# pcb5.net
KiCad netlist of a schematic drawn in EAGLE
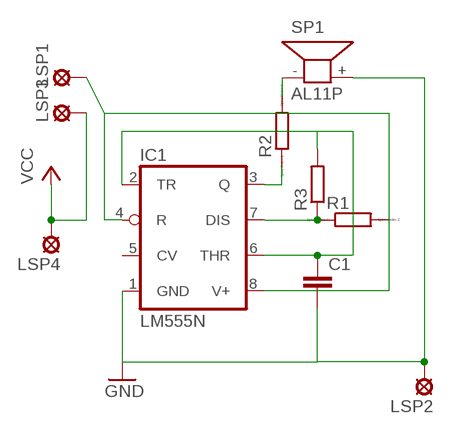
[diagram p0: schematic, sheet 1]

(export (version "E")
  (design (tool "Eeschema 10.0.6"))
  (components
    (comp (ref "C1")
      (value "C-EU025-024X044")
      (footprint "eagle-import:C025-024X044")
      (libsource (lib "eagle-import") (part "C-EU025-024X044"))
    )
    (comp (ref "IC1")
      (value "LM555N")
      (footprint "eagle-import:DIL08")
      (libsource (lib "eagle-import") (part "555NLM"))
    )
    (comp (ref "LSP1")
      (value "MCS08")
      (footprint "eagle-import:MCS08")
      (libsource (lib "eagle-import") (part "MCS08"))
    )
    (comp (ref "LSP2")
      (value "MCS08")
      (footprint "eagle-import:MCS08")
      (libsource (lib "eagle-import") (part "MCS08"))
    )
    (comp (ref "LSP3")
      (value "MCS08")
      (footprint "eagle-import:MCS08")
      (libsource (lib "eagle-import") (part "MCS08"))
    )
    (comp (ref "LSP4")
      (value "MCS08")
      (footprint "eagle-import:MCS08")
      (libsource (lib "eagle-import") (part "MCS08"))
    )
    (comp (ref "R1")
      (value "R-EU_0204_7")
      (footprint "eagle-import:0204_7")
      (libsource (lib "eagle-import") (part "R-EU_0204_7"))
    )
    (comp (ref "R2")
      (value "R-EU_0204_7")
      (footprint "eagle-import:0204_7")
      (libsource (lib "eagle-import") (part "R-EU_0204_7"))
    )
    (comp (ref "R3")
      (value "R-EU_0204/7")
      (footprint "eagle-import:0204_7")
      (libsource (lib "eagle-import") (part "R-EU_0204/7"))
    )
    (comp (ref "SP1")
      (value "AL11P")
      (footprint "eagle-import:AL11P")
      (libsource (lib "eagle-import") (part "AL11P"))
    )
  )
  (nets
    (net (code "1") (name "GND") (class "Default")
      (node (ref "C1") (pin "2") (pinfunction "2_2") (pintype "passive"))
      (node (ref "IC1") (pin "1") (pinfunction "GND_1") (pintype "power_in"))
      (node (ref "LSP2") (pin "MP") (pinfunction "MP_MP") (pintype "passive"))
      (node (ref "SP1") (pin "+") (pinfunction "2_+") (pintype "passive"))
    )
    (net (code "2") (name "Net-(IC1-DIS)") (class "Default")
      (node (ref "IC1") (pin "7") (pinfunction "DIS_7") (pintype "input"))
      (node (ref "R1") (pin "1") (pinfunction "1_1") (pintype "passive"))
      (node (ref "R3") (pin "1") (pinfunction "1_1") (pintype "passive"))
    )
    (net (code "3") (name "Net-(IC1-Q)") (class "Default")
      (node (ref "IC1") (pin "3") (pinfunction "Q_3") (pintype "output"))
      (node (ref "R2") (pin "1") (pinfunction "1_1") (pintype "passive"))
    )
    (net (code "4") (name "Net-(IC1-R)") (class "Default")
      (node (ref "IC1") (pin "4") (pinfunction "R_4") (pintype "input"))
      (node (ref "IC1") (pin "8") (pinfunction "V+_8") (pintype "power_in"))
      (node (ref "LSP1") (pin "MP") (pinfunction "MP_MP") (pintype "passive"))
      (node (ref "R1") (pin "2") (pinfunction "2_2") (pintype "passive"))
    )
    (net (code "5") (name "Net-(IC1-THR)") (class "Default")
      (node (ref "C1") (pin "1") (pinfunction "1_1") (pintype "passive"))
      (node (ref "IC1") (pin "2") (pinfunction "TR_2") (pintype "input"))
      (node (ref "IC1") (pin "6") (pinfunction "THR_6") (pintype "input"))
      (node (ref "R3") (pin "2") (pinfunction "2_2") (pintype "passive"))
    )
    (net (code "6") (name "Net-(SP1-1)") (class "Default")
      (node (ref "R2") (pin "2") (pinfunction "2_2") (pintype "passive"))
      (node (ref "SP1") (pin "-") (pinfunction "1_-") (pintype "passive"))
    )
    (net (code "7") (name "VCC") (class "Default")
      (node (ref "LSP3") (pin "MP") (pinfunction "MP_MP") (pintype "passive"))
      (node (ref "LSP4") (pin "MP") (pinfunction "MP_MP") (pintype "passive"))
    )
    (net (code "8") (name "unconnected-(IC1-CV-Pad5)") (class "Default")
      (node (ref "IC1") (pin "5") (pinfunction "CV_5") (pintype "input"))
    )
  )
)
